# SCH_water-temp_2026-06-27.net
KiCad netlist of a schematic drawn in EasyEDA
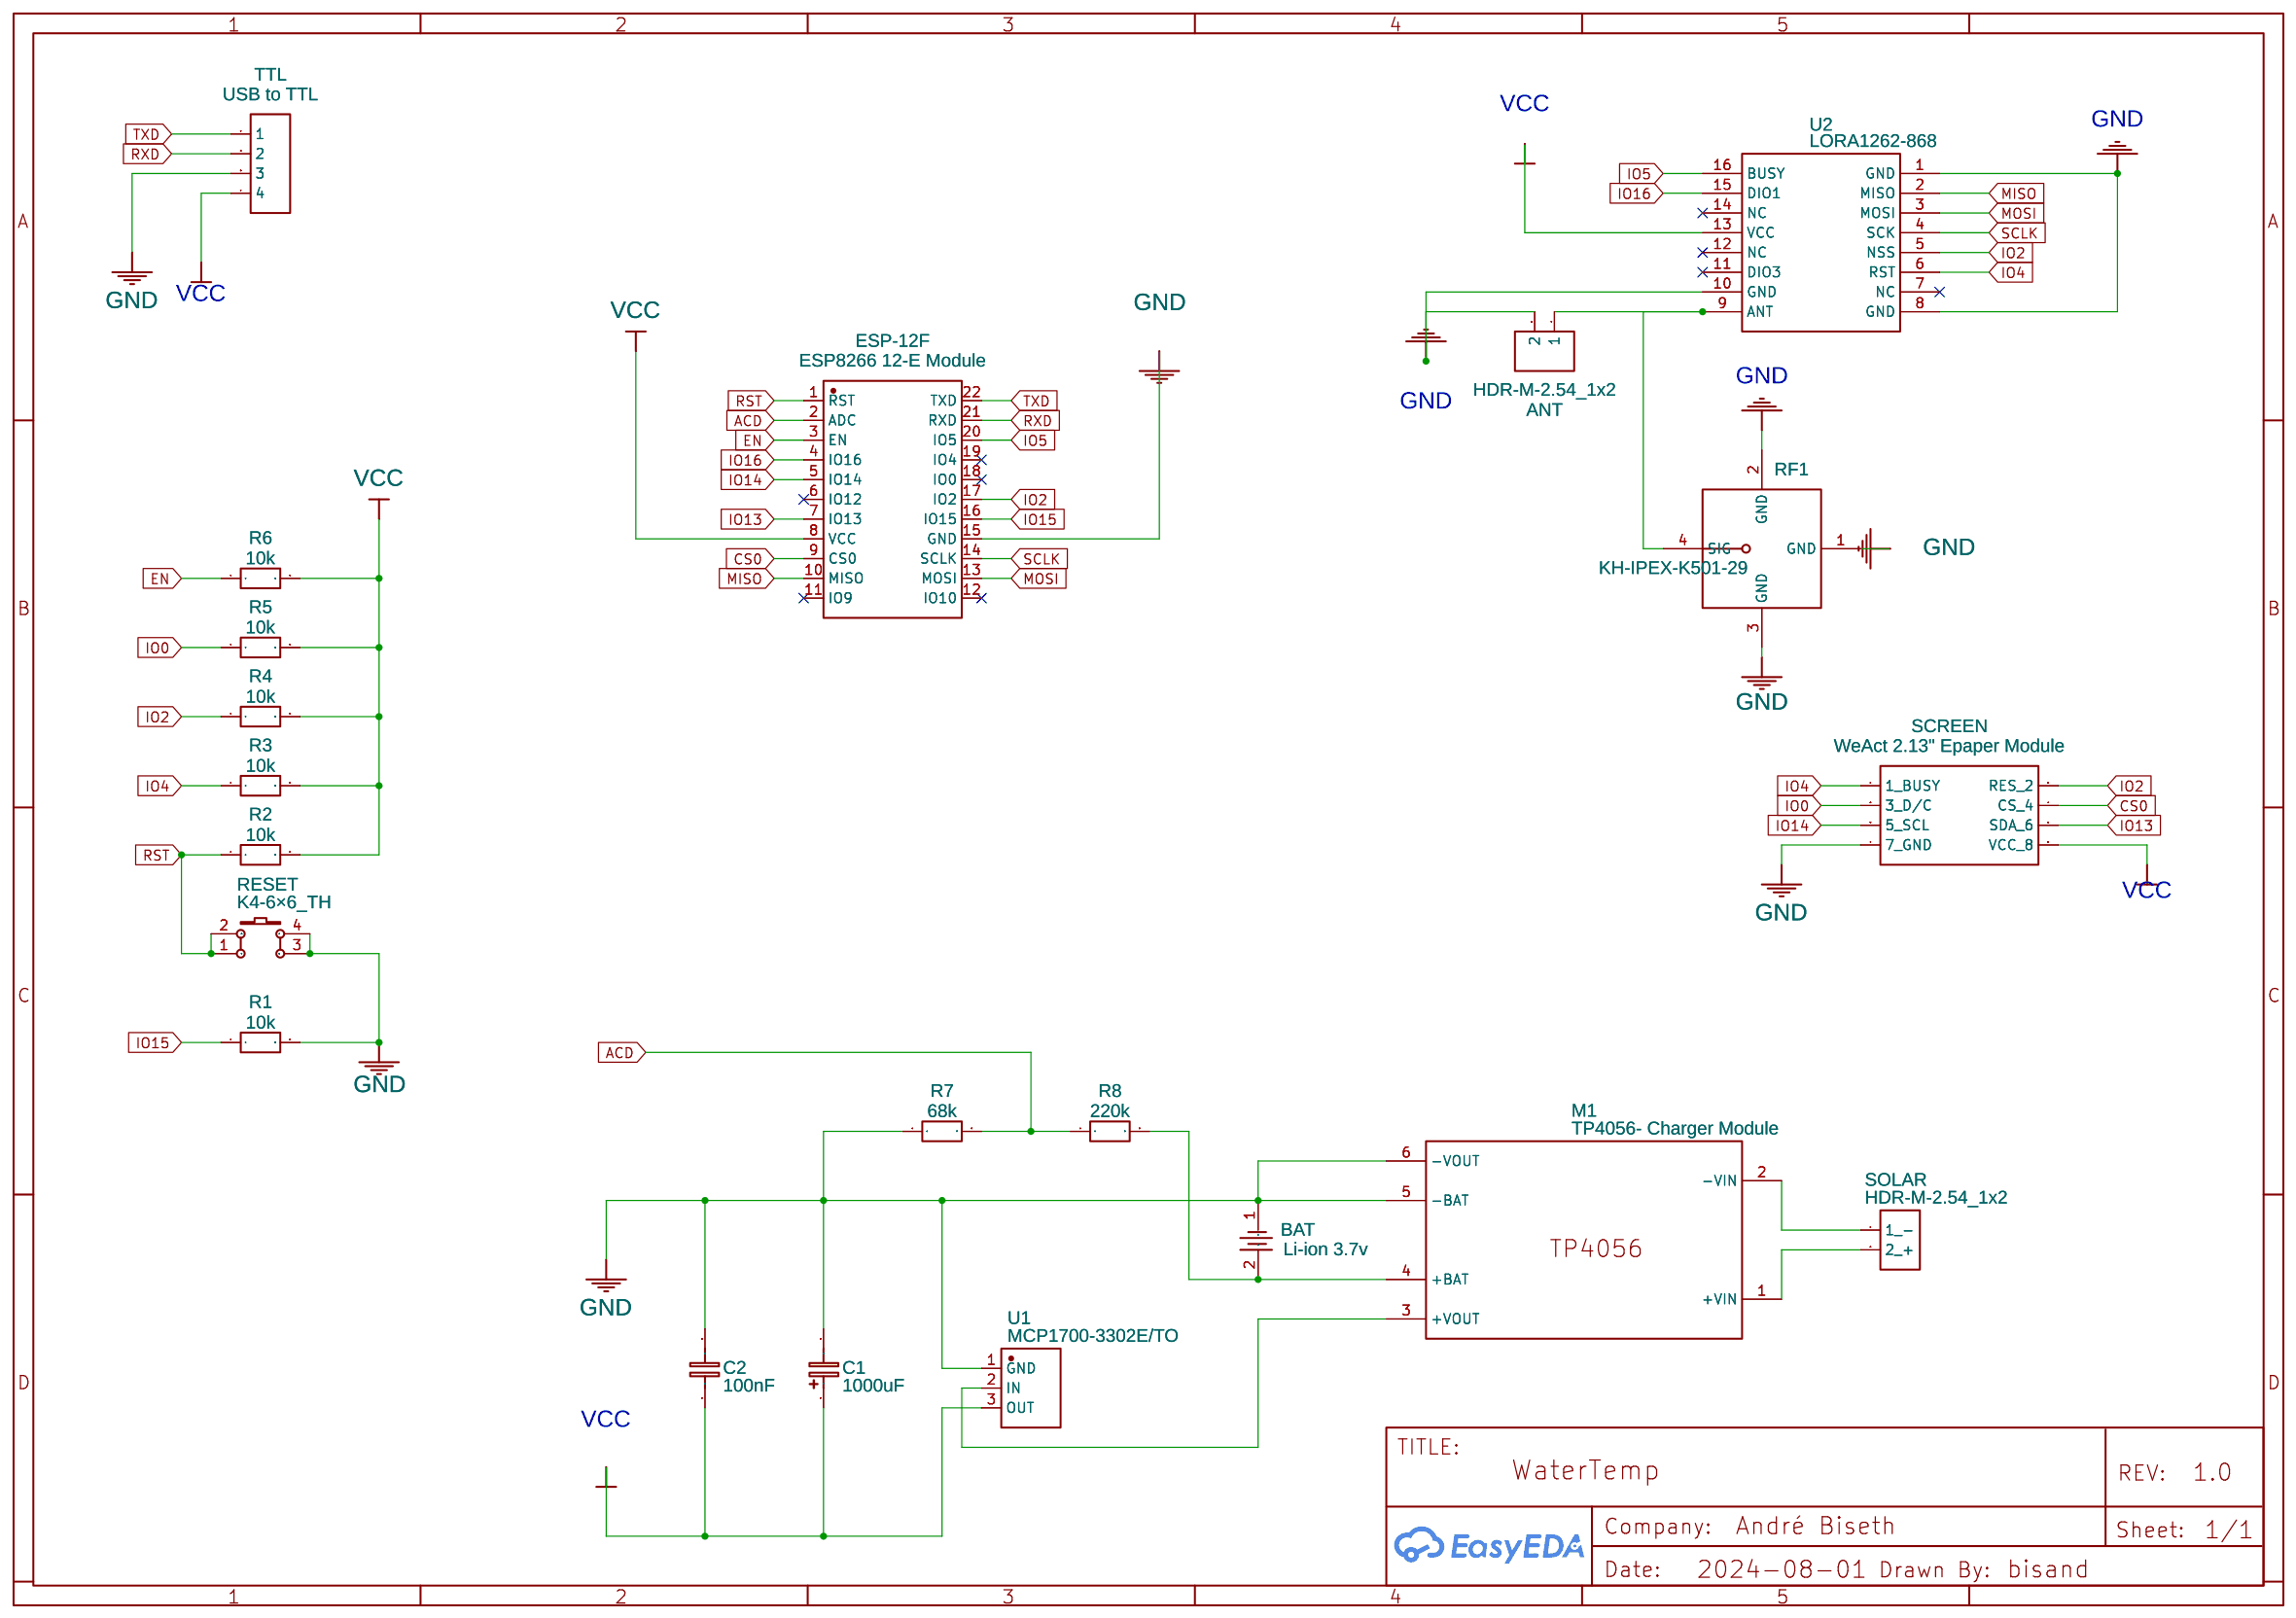
[diagram p0: schematic sheet]

(export (version "E")
  (design (tool "Eeschema 10.0.6"))
  (components
    (comp (ref "ANT") (value "HDR-M-2.54_1x2") (libsource (lib "") (part "HDR-M-2.54_1x2")))
    (comp (ref "BAT")
      (value "Li-ion 3.7v")
      (fields
        (field (name "Manufacturer Part") "BH-18650-B1BA002")
        (field (name "Manufacturer") "MYOUNG(美阳)")
      )
      (libsource (lib "") (part "BH-18650-B1BA002"))
    )
    (comp (ref "C1") (value "1000uF") (libsource (lib "") (part "CE_TH_D8.0×F3.5_EU")))
    (comp (ref "C2") (value "100nF") (libsource (lib "") (part "C_RAD-0.1_EU")))
    (comp (ref "ESP-12F")
      (value "ESP8266 12-E Module")
      (fields (field (name "Manufacturer Part") "ESP-12E") (field (name "Manufacturer") "Ai-Thinker(安信可)"))
      (libsource (lib "") (part "ESP-12E"))
    )
    (comp (ref "M1")
      (value "TP4056- Charger Module")
      (fields (field (name "Manufacturer") "China"))
      (libsource (lib "") (part "TP4056- Charger Module"))
    )
    (comp (ref "R1") (value "10k") (libsource (lib "") (part "R_AXIAL-0.3_EU")))
    (comp (ref "R2") (value "10k") (libsource (lib "") (part "R_AXIAL-0.3_EU")))
    (comp (ref "R3") (value "10k") (libsource (lib "") (part "R_AXIAL-0.3_EU")))
    (comp (ref "R4") (value "10k") (libsource (lib "") (part "R_AXIAL-0.3_EU")))
    (comp (ref "R5") (value "10k") (libsource (lib "") (part "R_AXIAL-0.3_EU")))
    (comp (ref "R6") (value "10k") (libsource (lib "") (part "R_AXIAL-0.3_EU")))
    (comp (ref "R7") (value "68k") (libsource (lib "") (part "R_AXIAL-0.4_EU")))
    (comp (ref "R8") (value "220k") (libsource (lib "") (part "R_AXIAL-0.4_EU")))
    (comp (ref "RESET")
      (value "K4-6×6_TH")
      (fields (field (name "Manufacturer Part") "K2-1102DP-E4SW-04") (field (name "Manufacturer") "韩国韩荣"))
      (libsource (lib "") (part "K4-6×6_TH"))
    )
    (comp (ref "RF1")
      (value "KH-IPEX-K501-29")
      (fields (field (name "Manufacturer") "kinghelm(金航标)"))
      (libsource (lib "") (part "KH-IPEX-K501-29"))
    )
    (comp (ref "SCREEN")
      (value "WeAct 2.13\" Epaper Module")
      (fields (field (name "Manufacturer Part") "ld-213ei-bw") (field (name "Manufacturer") "WeAct Studio"))
      (libsource (lib "") (part "WeAct 2.13{dblquote} Epaper Module"))
    )
    (comp (ref "SOLAR") (value "HDR-M-2.54_1x2") (libsource (lib "") (part "HDR-M-2.54_1x2_1")))
    (comp (ref "TTL") (value "USB to TTL") (libsource (lib "") (part "HDR-M-2.54_1x4")))
    (comp (ref "U1")
      (value "MCP1700-3302E/TO")
      (fields (field (name "Manufacturer") "MICROCHIP(美国微芯)"))
      (libsource (lib "") (part "MCP1700-3302E/TO"))
    )
    (comp (ref "U2") (value "LORA1262-868") (libsource (lib "") (part "LORA1262-868")))
  )
  (nets
    (net (code "1") (name "ACD") (class "Default")
      (node (ref "ESP-12F") (pin "2") (pinfunction "ADC_2") (pintype "unspecified"))
      (node (ref "R7") (pin "2") (pinfunction "2_2") (pintype "unspecified"))
      (node (ref "R8") (pin "1") (pinfunction "1_1") (pintype "unspecified"))
    )
    (net (code "2") (name "CS0") (class "Default")
      (node (ref "ESP-12F") (pin "9") (pinfunction "CS0_9") (pintype "unspecified"))
      (node (ref "SCREEN") (pin "4") (pinfunction "CS_4_4") (pintype "unspecified"))
    )
    (net (code "3") (name "EN") (class "Default")
      (node (ref "ESP-12F") (pin "3") (pinfunction "EN_3") (pintype "unspecified"))
      (node (ref "R6") (pin "1") (pinfunction "1_1") (pintype "unspecified"))
    )
    (net (code "4") (name "GND") (class "Default")
      (node (ref "ANT") (pin "2") (pinfunction "2_2") (pintype "unspecified"))
      (node (ref "BAT") (pin "1") (pinfunction "1_1") (pintype "input"))
      (node (ref "C1") (pin "2") (pinfunction "2_2") (pintype "unspecified"))
      (node (ref "C2") (pin "2") (pinfunction "2_2") (pintype "unspecified"))
      (node (ref "ESP-12F") (pin "15") (pinfunction "GND_15") (pintype "unspecified"))
      (node (ref "M1") (pin "5") (pinfunction "-BAT_5") (pintype "unspecified"))
      (node (ref "M1") (pin "6") (pinfunction "-VOUT_6") (pintype "unspecified"))
      (node (ref "R1") (pin "2") (pinfunction "2_2") (pintype "unspecified"))
      (node (ref "R7") (pin "1") (pinfunction "1_1") (pintype "unspecified"))
      (node (ref "RESET") (pin "3") (pinfunction "3_3") (pintype "unspecified"))
      (node (ref "RESET") (pin "4") (pinfunction "4_4") (pintype "unspecified"))
      (node (ref "RF1") (pin "1") (pinfunction "GND_1") (pintype "unspecified"))
      (node (ref "RF1") (pin "2") (pinfunction "GND_2") (pintype "unspecified"))
      (node (ref "RF1") (pin "3") (pinfunction "GND_3") (pintype "unspecified"))
      (node (ref "SCREEN") (pin "7") (pinfunction "7_GND_7") (pintype "unspecified"))
      (node (ref "TTL") (pin "3") (pinfunction "3_3") (pintype "unspecified"))
      (node (ref "U1") (pin "1") (pinfunction "GND_1") (pintype "unspecified"))
      (node (ref "U2") (pin "1") (pinfunction "GND_1") (pintype "unspecified"))
      (node (ref "U2") (pin "10") (pinfunction "GND_10") (pintype "unspecified"))
      (node (ref "U2") (pin "8") (pinfunction "GND_8") (pintype "unspecified"))
    )
    (net (code "5") (name "IO0") (class "Default")
      (node (ref "R5") (pin "1") (pinfunction "1_1") (pintype "unspecified"))
      (node (ref "SCREEN") (pin "3") (pinfunction "3_D/C_3") (pintype "unspecified"))
    )
    (net (code "6") (name "IO2") (class "Default")
      (node (ref "ESP-12F") (pin "17") (pinfunction "IO2_17") (pintype "unspecified"))
      (node (ref "R4") (pin "1") (pinfunction "1_1") (pintype "unspecified"))
      (node (ref "SCREEN") (pin "2") (pinfunction "RES_2_2") (pintype "unspecified"))
      (node (ref "U2") (pin "5") (pinfunction "NSS_5") (pintype "unspecified"))
    )
    (net (code "7") (name "IO4") (class "Default")
      (node (ref "R3") (pin "1") (pinfunction "1_1") (pintype "unspecified"))
      (node (ref "SCREEN") (pin "1") (pinfunction "1_BUSY_1") (pintype "unspecified"))
      (node (ref "U2") (pin "6") (pinfunction "RST_6") (pintype "unspecified"))
    )
    (net (code "8") (name "IO5") (class "Default")
      (node (ref "ESP-12F") (pin "20") (pinfunction "IO5_20") (pintype "unspecified"))
      (node (ref "U2") (pin "16") (pinfunction "BUSY_16") (pintype "unspecified"))
    )
    (net (code "9") (name "IO13") (class "Default")
      (node (ref "ESP-12F") (pin "7") (pinfunction "IO13_7") (pintype "unspecified"))
      (node (ref "SCREEN") (pin "6") (pinfunction "SDA_6_6") (pintype "unspecified"))
    )
    (net (code "10") (name "IO14") (class "Default")
      (node (ref "ESP-12F") (pin "5") (pinfunction "IO14_5") (pintype "unspecified"))
      (node (ref "SCREEN") (pin "5") (pinfunction "5_SCL_5") (pintype "unspecified"))
    )
    (net (code "11") (name "IO15") (class "Default")
      (node (ref "ESP-12F") (pin "16") (pinfunction "IO15_16") (pintype "unspecified"))
      (node (ref "R1") (pin "1") (pinfunction "1_1") (pintype "unspecified"))
    )
    (net (code "12") (name "IO16") (class "Default")
      (node (ref "ESP-12F") (pin "4") (pinfunction "IO16_4") (pintype "unspecified"))
      (node (ref "U2") (pin "15") (pinfunction "DIO1_15") (pintype "unspecified"))
    )
    (net (code "13") (name "MISO") (class "Default")
      (node (ref "ESP-12F") (pin "10") (pinfunction "MISO_10") (pintype "unspecified"))
      (node (ref "U2") (pin "2") (pinfunction "MISO_2") (pintype "unspecified"))
    )
    (net (code "14") (name "MOSI") (class "Default")
      (node (ref "ESP-12F") (pin "13") (pinfunction "MOSI_13") (pintype "unspecified"))
      (node (ref "U2") (pin "3") (pinfunction "MOSI_3") (pintype "unspecified"))
    )
    (net (code "15") (name "Net-(M1-+BAT)") (class "Default")
      (node (ref "BAT") (pin "2") (pinfunction "2_2") (pintype "input"))
      (node (ref "M1") (pin "4") (pinfunction "+BAT_4") (pintype "unspecified"))
      (node (ref "R8") (pin "2") (pinfunction "2_2") (pintype "unspecified"))
    )
    (net (code "16") (name "Net-(M1-+VIN)") (class "Default")
      (node (ref "M1") (pin "1") (pinfunction "+VIN_1") (pintype "unspecified"))
      (node (ref "SOLAR") (pin "2") (pinfunction "2_+_2") (pintype "unspecified"))
    )
    (net (code "17") (name "Net-(M1-+VOUT)") (class "Default")
      (node (ref "M1") (pin "3") (pinfunction "+VOUT_3") (pintype "unspecified"))
      (node (ref "U1") (pin "2") (pinfunction "IN_2") (pintype "unspecified"))
    )
    (net (code "18") (name "Net-(M1--VIN)") (class "Default")
      (node (ref "M1") (pin "2") (pinfunction "-VIN_2") (pintype "unspecified"))
      (node (ref "SOLAR") (pin "1") (pinfunction "1_-_1") (pintype "unspecified"))
    )
    (net (code "19") (name "Net-(RF1-SIG)") (class "Default")
      (node (ref "ANT") (pin "1") (pinfunction "1_1") (pintype "unspecified"))
      (node (ref "RF1") (pin "4") (pinfunction "SIG_4") (pintype "unspecified"))
      (node (ref "U2") (pin "9") (pinfunction "ANT_9") (pintype "unspecified"))
    )
    (net (code "20") (name "RST") (class "Default")
      (node (ref "ESP-12F") (pin "1") (pinfunction "RST_1") (pintype "unspecified"))
      (node (ref "R2") (pin "1") (pinfunction "1_1") (pintype "unspecified"))
      (node (ref "RESET") (pin "1") (pinfunction "1_1") (pintype "unspecified"))
      (node (ref "RESET") (pin "2") (pinfunction "2_2") (pintype "unspecified"))
    )
    (net (code "21") (name "RXD") (class "Default")
      (node (ref "ESP-12F") (pin "21") (pinfunction "RXD_21") (pintype "unspecified"))
      (node (ref "TTL") (pin "2") (pinfunction "2_2") (pintype "unspecified"))
    )
    (net (code "22") (name "SCLK") (class "Default")
      (node (ref "ESP-12F") (pin "14") (pinfunction "SCLK_14") (pintype "unspecified"))
      (node (ref "U2") (pin "4") (pinfunction "SCK_4") (pintype "unspecified"))
    )
    (net (code "23") (name "TXD") (class "Default")
      (node (ref "ESP-12F") (pin "22") (pinfunction "TXD_22") (pintype "unspecified"))
      (node (ref "TTL") (pin "1") (pinfunction "1_1") (pintype "unspecified"))
    )
    (net (code "24") (name "VCC") (class "Default")
      (node (ref "C1") (pin "1") (pinfunction "1_1") (pintype "unspecified"))
      (node (ref "C2") (pin "1") (pinfunction "1_1") (pintype "unspecified"))
      (node (ref "ESP-12F") (pin "8") (pinfunction "VCC_8") (pintype "unspecified"))
      (node (ref "R2") (pin "2") (pinfunction "2_2") (pintype "unspecified"))
      (node (ref "R3") (pin "2") (pinfunction "2_2") (pintype "unspecified"))
      (node (ref "R4") (pin "2") (pinfunction "2_2") (pintype "unspecified"))
      (node (ref "R5") (pin "2") (pinfunction "2_2") (pintype "unspecified"))
      (node (ref "R6") (pin "2") (pinfunction "2_2") (pintype "unspecified"))
      (node (ref "SCREEN") (pin "8") (pinfunction "VCC_8_8") (pintype "passive"))
      (node (ref "TTL") (pin "4") (pinfunction "4_4") (pintype "unspecified"))
      (node (ref "U1") (pin "3") (pinfunction "OUT_3") (pintype "unspecified"))
      (node (ref "U2") (pin "13") (pinfunction "VCC_13") (pintype "unspecified"))
    )
    (net (code "25") (name "unconnected-(ESP-12F-IO0-Pad18)") (class "Default")
      (node (ref "ESP-12F") (pin "18") (pinfunction "IO0_18") (pintype "unspecified+no_connect"))
    )
    (net (code "26") (name "unconnected-(ESP-12F-IO4-Pad19)") (class "Default")
      (node (ref "ESP-12F") (pin "19") (pinfunction "IO4_19") (pintype "unspecified+no_connect"))
    )
    (net (code "27") (name "unconnected-(ESP-12F-IO9-Pad11)") (class "Default")
      (node (ref "ESP-12F") (pin "11") (pinfunction "IO9_11") (pintype "unspecified+no_connect"))
    )
    (net (code "28") (name "unconnected-(ESP-12F-IO10-Pad12)") (class "Default")
      (node (ref "ESP-12F") (pin "12") (pinfunction "IO10_12") (pintype "unspecified+no_connect"))
    )
    (net (code "29") (name "unconnected-(ESP-12F-IO12-Pad6)") (class "Default")
      (node (ref "ESP-12F") (pin "6") (pinfunction "IO12_6") (pintype "unspecified+no_connect"))
    )
    (net (code "30") (name "unconnected-(U2-DIO3-Pad11)") (class "Default")
      (node (ref "U2") (pin "11") (pinfunction "DIO3_11") (pintype "unspecified+no_connect"))
    )
    (net (code "31") (name "unconnected-(U2-NC-Pad7)") (class "Default")
      (node (ref "U2") (pin "7") (pinfunction "NC_7") (pintype "unspecified+no_connect"))
    )
    (net (code "32") (name "unconnected-(U2-NC-Pad12)") (class "Default")
      (node (ref "U2") (pin "12") (pinfunction "NC_12") (pintype "unspecified+no_connect"))
    )
    (net (code "33") (name "unconnected-(U2-NC-Pad14)") (class "Default")
      (node (ref "U2") (pin "14") (pinfunction "NC_14") (pintype "unspecified+no_connect"))
    )
  )
)
